# TSOC_GROVEY_I2CHUB.net
KiCad netlist of a schematic drawn in EAGLE
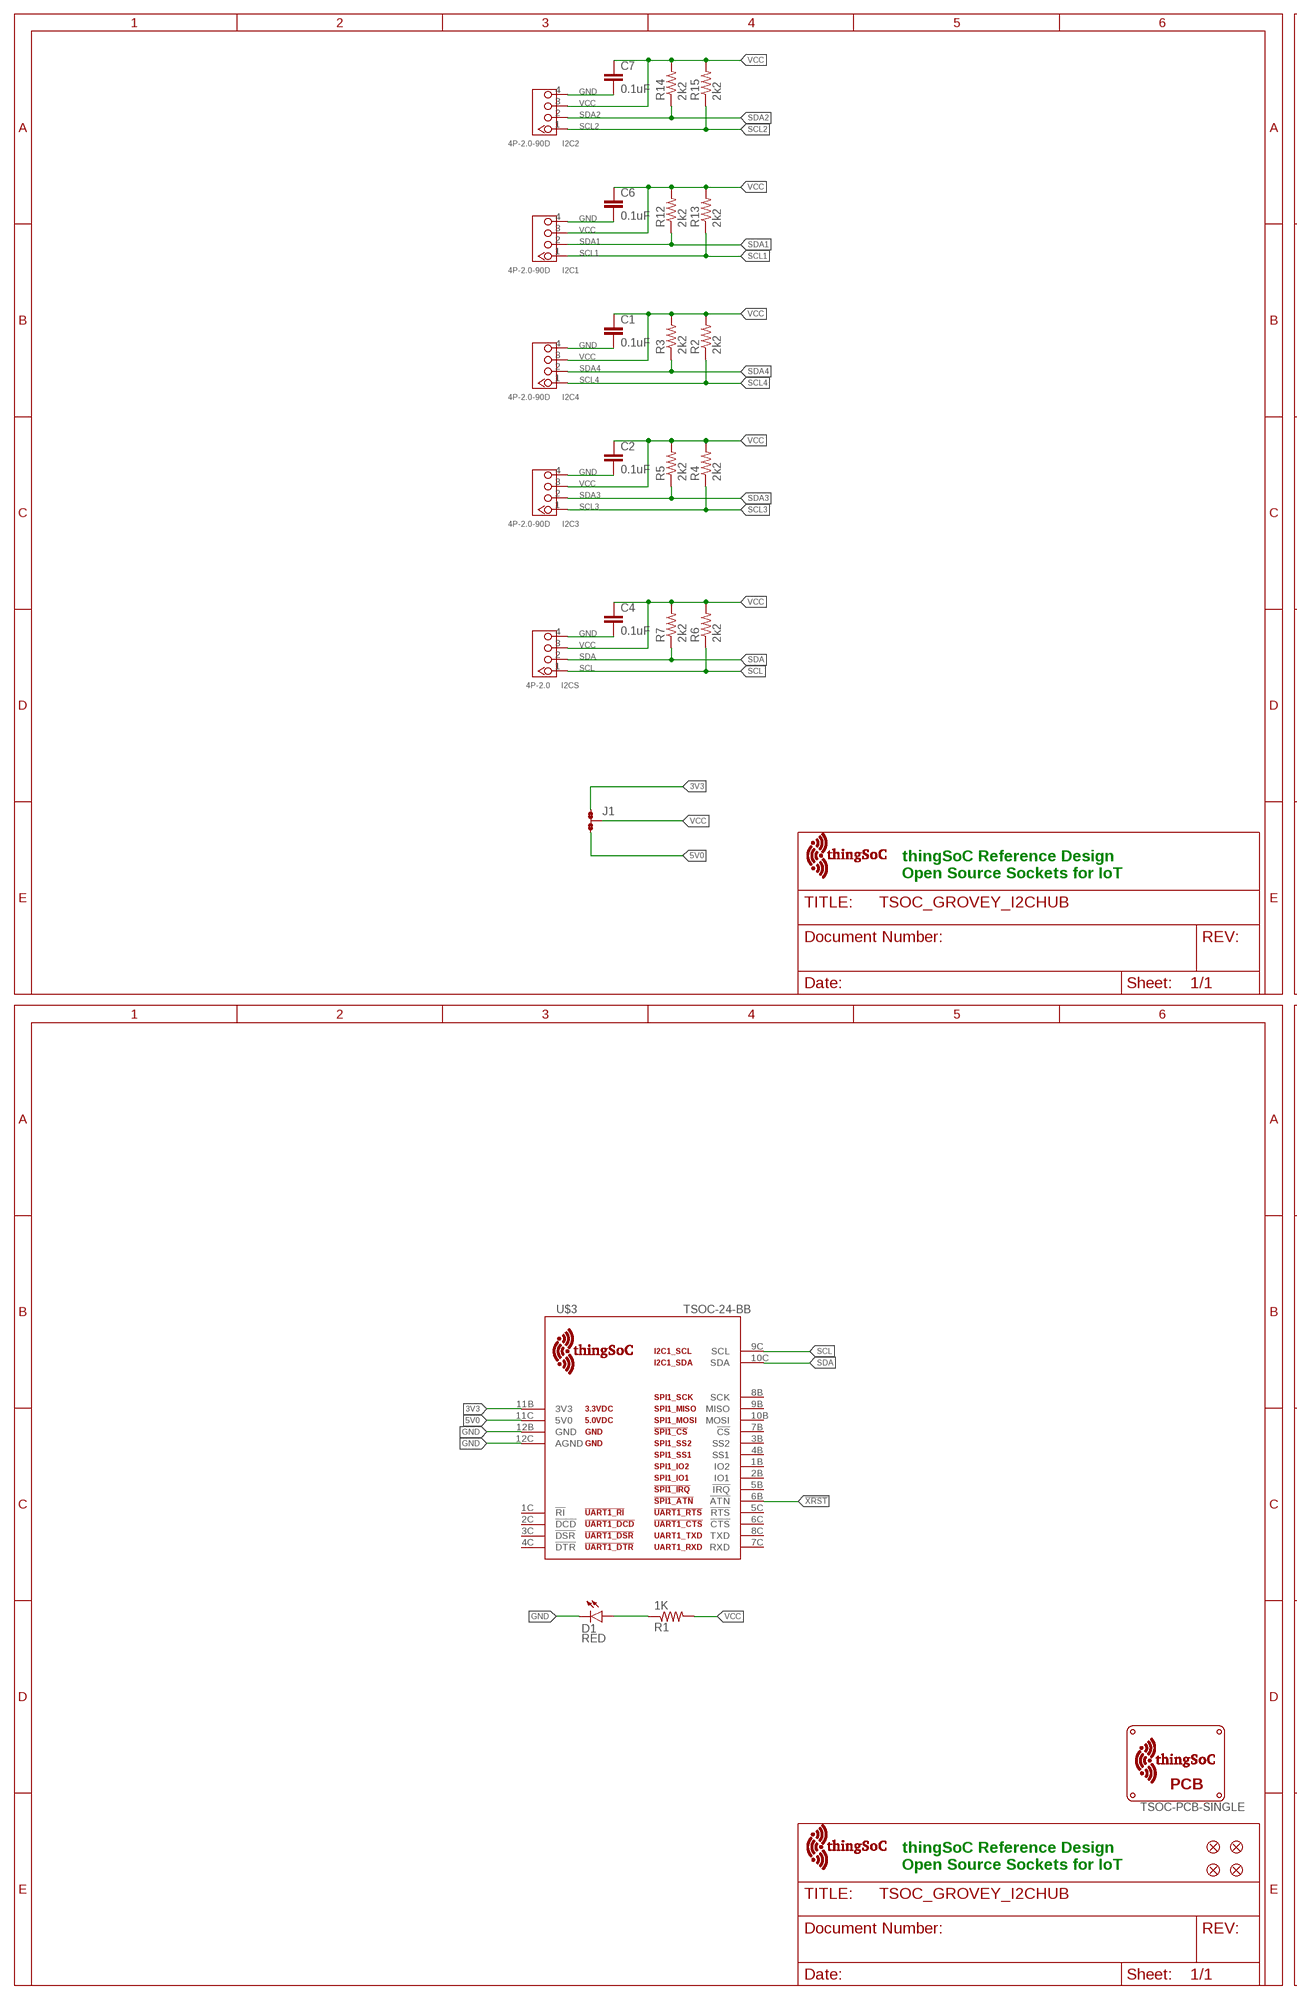
[diagram p0: schematic, sheet 1, part 1 of 2]
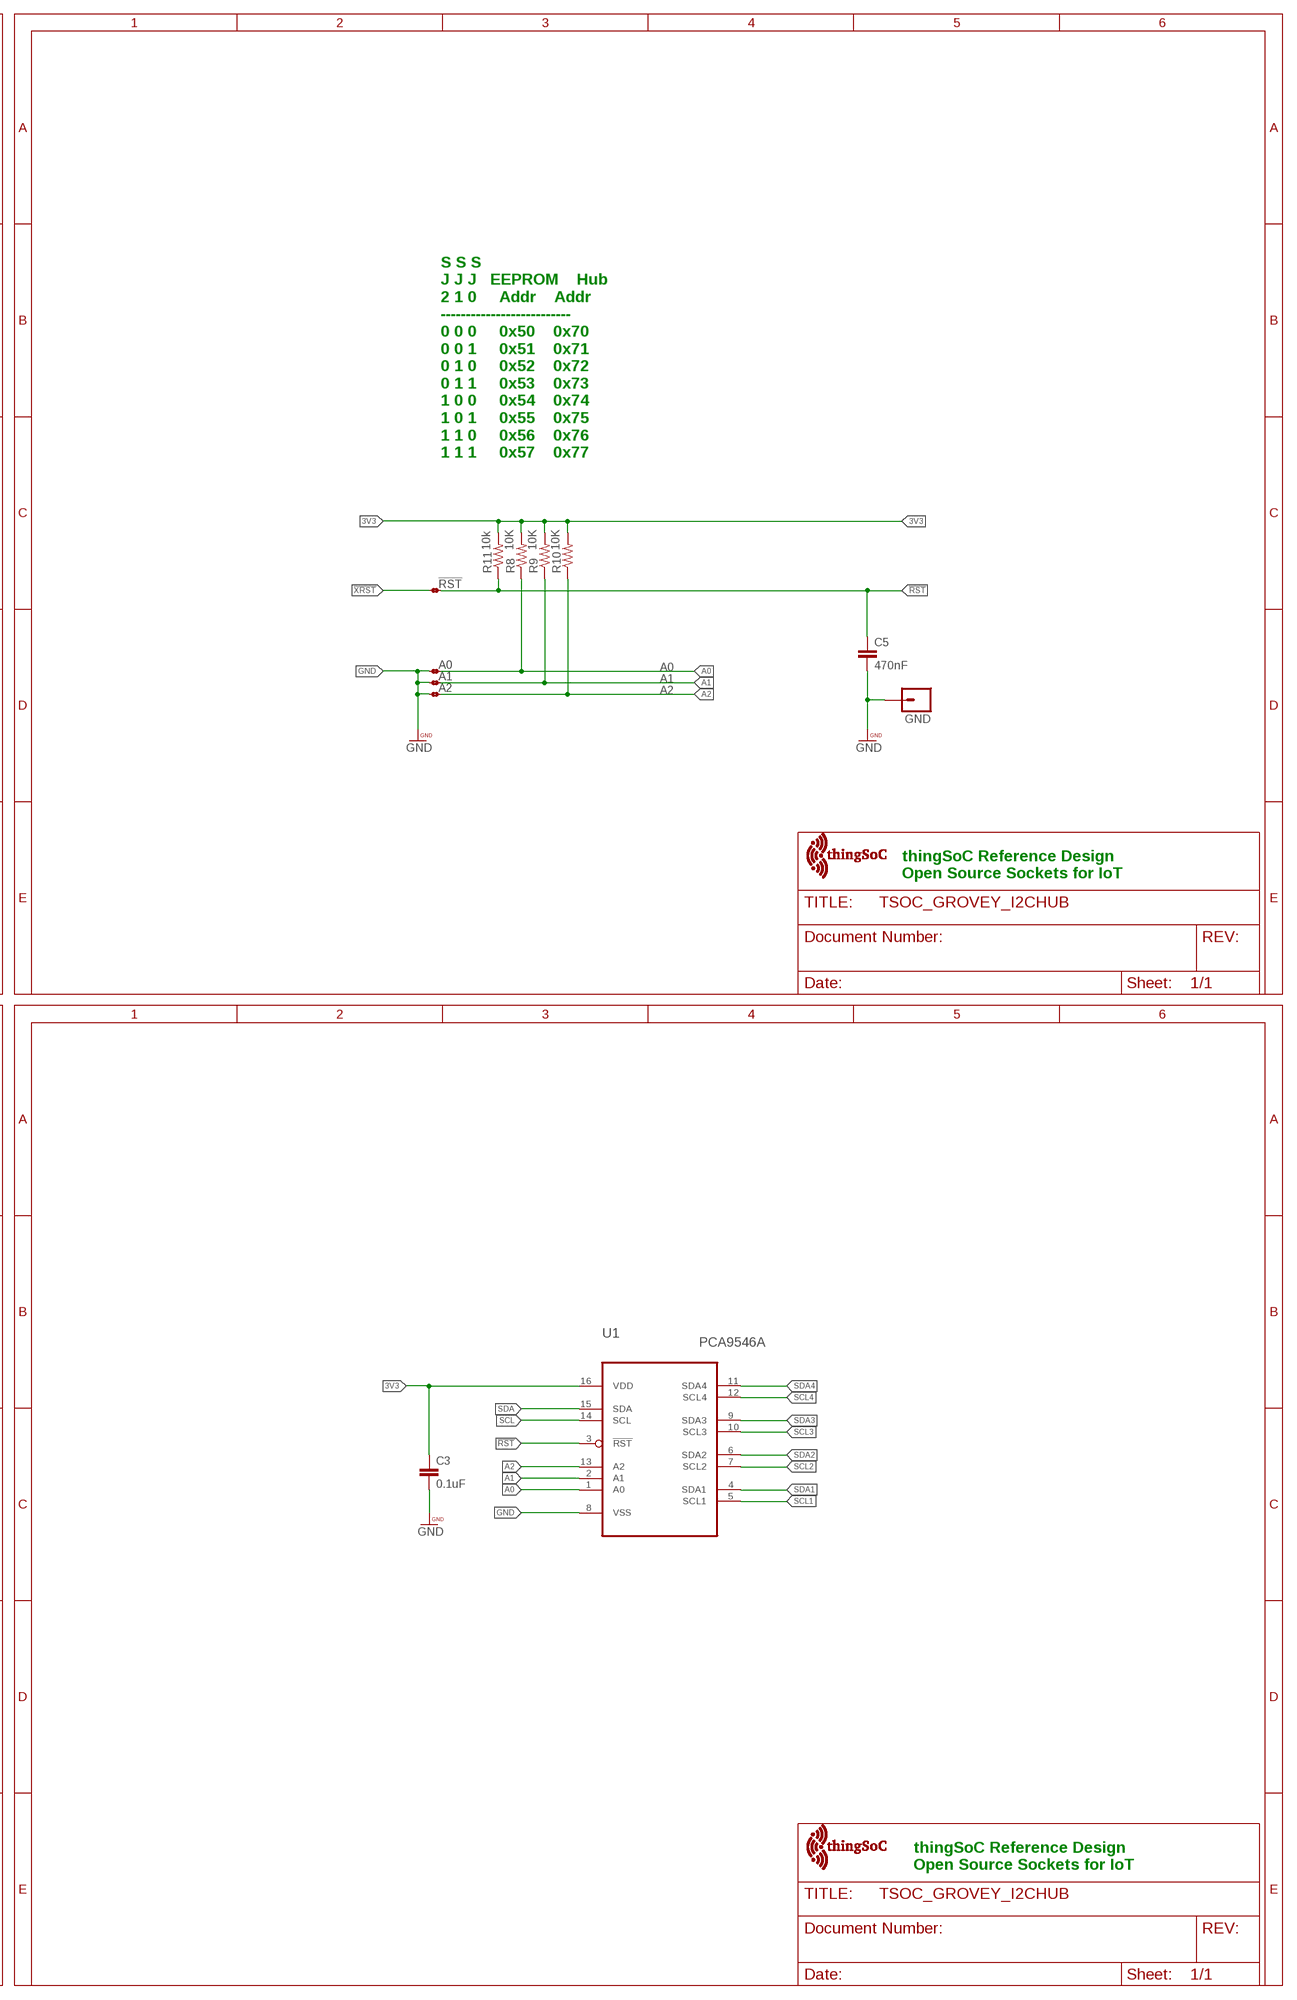
[diagram p1: schematic, sheet 1, part 2 of 2]

(export (version "E")
  (design (tool "Eeschema 10.0.6"))
  (components
    (comp (ref "!RST")
      (value "NO")
      (footprint "eagle-import:JMP-2-NO")
      (libsource (lib "eagle-import") (part "JMP-2-NO"))
    )
    (comp (ref "A0")
      (value "NO")
      (footprint "eagle-import:JMP-2-NO")
      (libsource (lib "eagle-import") (part "JMP-2-NO"))
    )
    (comp (ref "A1")
      (value "NO")
      (footprint "eagle-import:JMP-2-NO")
      (libsource (lib "eagle-import") (part "JMP-2-NO"))
    )
    (comp (ref "A2")
      (value "NO")
      (footprint "eagle-import:JMP-2-NO")
      (libsource (lib "eagle-import") (part "JMP-2-NO"))
    )
    (comp (ref "C1")
      (value "0.1uF")
      (footprint "eagle-import:0603-CAP")
      (libsource (lib "eagle-import") (part "CAP0603-CAP"))
    )
    (comp (ref "C2")
      (value "0.1uF")
      (footprint "eagle-import:0603-CAP")
      (libsource (lib "eagle-import") (part "CAP0603-CAP"))
    )
    (comp (ref "C3")
      (value "0.1uF")
      (footprint "eagle-import:0603-CAP")
      (libsource (lib "eagle-import") (part "CAP0603-CAP"))
    )
    (comp (ref "C4")
      (value "0.1uF")
      (footprint "eagle-import:0603-CAP")
      (libsource (lib "eagle-import") (part "CAP0603-CAP"))
    )
    (comp (ref "C5")
      (value "470nF")
      (footprint "eagle-import:0603-CAP")
      (libsource (lib "eagle-import") (part "CAP0603-CAP"))
    )
    (comp (ref "C6")
      (value "0.1uF")
      (footprint "eagle-import:0603-CAP")
      (libsource (lib "eagle-import") (part "CAP0603-CAP"))
    )
    (comp (ref "C7")
      (value "0.1uF")
      (footprint "eagle-import:0603-CAP")
      (libsource (lib "eagle-import") (part "CAP0603-CAP"))
    )
    (comp (ref "D1")
      (value "RED")
      (footprint "eagle-import:LED-0603")
      (libsource (lib "eagle-import") (part "LED0603"))
    )
    (comp (ref "FID1")
      (value "FIDUCIALUFIDUCIAL")
      (footprint "eagle-import:MICRO-FIDUCIAL")
      (libsource (lib "eagle-import") (part "FIDUCIALUFIDUCIAL"))
    )
    (comp (ref "FID2")
      (value "FIDUCIALUFIDUCIAL")
      (footprint "eagle-import:MICRO-FIDUCIAL")
      (libsource (lib "eagle-import") (part "FIDUCIALUFIDUCIAL"))
    )
    (comp (ref "FID3")
      (value "FIDUCIALUFIDUCIAL")
      (footprint "eagle-import:MICRO-FIDUCIAL")
      (libsource (lib "eagle-import") (part "FIDUCIALUFIDUCIAL"))
    )
    (comp (ref "FID4")
      (value "FIDUCIALUFIDUCIAL")
      (footprint "eagle-import:MICRO-FIDUCIAL")
      (libsource (lib "eagle-import") (part "FIDUCIALUFIDUCIAL"))
    )
    (comp (ref "GND")
      (value "M01PTH")
      (footprint "eagle-import:1X01")
      (libsource (lib "eagle-import") (part "M01PTH"))
    )
    (comp (ref "I2C1")
      (value "4P-2.0-90D")
      (footprint "eagle-import:HW4-2.0-90D")
      (libsource (lib "eagle-import") (part "GROVE-CONNECTOR-DIP-90D(4P-2.0)"))
    )
    (comp (ref "I2C2")
      (value "4P-2.0-90D")
      (footprint "eagle-import:HW4-2.0-90D")
      (libsource (lib "eagle-import") (part "GROVE-CONNECTOR-DIP-90D(4P-2.0)"))
    )
    (comp (ref "I2C3")
      (value "4P-2.0-90D")
      (footprint "eagle-import:HW4-2.0-90D")
      (libsource (lib "eagle-import") (part "GROVE-CONNECTOR-DIP-90D(4P-2.0)"))
    )
    (comp (ref "I2C4")
      (value "4P-2.0-90D")
      (footprint "eagle-import:HW4-2.0-90D")
      (libsource (lib "eagle-import") (part "GROVE-CONNECTOR-DIP-90D(4P-2.0)"))
    )
    (comp (ref "I2CS")
      (value "4P-2.0")
      (footprint "eagle-import:HW4-2.0")
      (libsource (lib "eagle-import") (part "GROVE-CONNECTOR-DIP(4P-2.0)"))
    )
    (comp (ref "J1")
      (value "NO")
      (footprint "eagle-import:JMP-3-NO-PTH-2.54")
      (libsource (lib "eagle-import") (part "JMP-3-NO-PTH"))
    )
    (comp (ref "R1")
      (value "1K")
      (footprint "eagle-import:0603-RES")
      (libsource (lib "eagle-import") (part "RESISTOR_SFE0603-RES"))
    )
    (comp (ref "R2")
      (value "2k2")
      (footprint "eagle-import:0603-RES")
      (libsource (lib "eagle-import") (part "RESISTOR0603-RES"))
    )
    (comp (ref "R3")
      (value "2k2")
      (footprint "eagle-import:0603-RES")
      (libsource (lib "eagle-import") (part "RESISTOR0603-RES"))
    )
    (comp (ref "R4")
      (value "2k2")
      (footprint "eagle-import:0603-RES")
      (libsource (lib "eagle-import") (part "RESISTOR0603-RES"))
    )
    (comp (ref "R5")
      (value "2k2")
      (footprint "eagle-import:0603-RES")
      (libsource (lib "eagle-import") (part "RESISTOR0603-RES"))
    )
    (comp (ref "R6")
      (value "2k2")
      (footprint "eagle-import:0603-RES")
      (libsource (lib "eagle-import") (part "RESISTOR0603-RES"))
    )
    (comp (ref "R7")
      (value "2k2")
      (footprint "eagle-import:0603-RES")
      (libsource (lib "eagle-import") (part "RESISTOR0603-RES"))
    )
    (comp (ref "R8")
      (value "10K")
      (footprint "eagle-import:0603-RES")
      (libsource (lib "eagle-import") (part "RESISTOR0603-RES"))
    )
    (comp (ref "R9")
      (value "10K")
      (footprint "eagle-import:0603-RES")
      (libsource (lib "eagle-import") (part "RESISTOR0603-RES"))
    )
    (comp (ref "R10")
      (value "10K")
      (footprint "eagle-import:0603-RES")
      (libsource (lib "eagle-import") (part "RESISTOR0603-RES"))
    )
    (comp (ref "R11")
      (value "10k")
      (footprint "eagle-import:0603-RES")
      (libsource (lib "eagle-import") (part "RESISTOR0603-RES"))
    )
    (comp (ref "R12")
      (value "2k2")
      (footprint "eagle-import:0603-RES")
      (libsource (lib "eagle-import") (part "RESISTOR0603-RES"))
    )
    (comp (ref "R13")
      (value "2k2")
      (footprint "eagle-import:0603-RES")
      (libsource (lib "eagle-import") (part "RESISTOR0603-RES"))
    )
    (comp (ref "R14")
      (value "2k2")
      (footprint "eagle-import:0603-RES")
      (libsource (lib "eagle-import") (part "RESISTOR0603-RES"))
    )
    (comp (ref "R15")
      (value "2k2")
      (footprint "eagle-import:0603-RES")
      (libsource (lib "eagle-import") (part "RESISTOR0603-RES"))
    )
    (comp (ref "U$1")
      (value "TSOC-LOGO-SMALL")
      (footprint "eagle-import:TSOC-LOGO-SML")
      (libsource (lib "eagle-import") (part "TSOC-LOGO-SMALL"))
    )
    (comp (ref "U$2")
      (value "TSOC-PCB-SINGLE")
      (footprint "eagle-import:TSOC-BB-BRD-DIM")
      (libsource (lib "eagle-import") (part "TSOC-PCB-SINGLE"))
    )
    (comp (ref "U$3")
      (value "TSOC-24-BB")
      (footprint "eagle-import:TSOC-BB-S24")
      (libsource (lib "eagle-import") (part "TSOC-24-BB"))
    )
    (comp (ref "U$101")
      (value "TSOC-LOGO-LRG")
      (footprint "eagle-import:TSOC-LOGO-LRG")
      (libsource (lib "eagle-import") (part "TSOC-LOGO-LRG"))
    )
    (comp (ref "U$102")
      (value "TSOC-LOGO-SMALL")
      (footprint "eagle-import:TSOC-LOGO-SML")
      (libsource (lib "eagle-import") (part "TSOC-LOGO-SMALL"))
    )
    (comp (ref "U$103")
      (value "TSOC-LOGO-SMALL")
      (footprint "eagle-import:TSOC-LOGO-SML")
      (libsource (lib "eagle-import") (part "TSOC-LOGO-SMALL"))
    )
    (comp (ref "U1")
      (value "PCA9546A")
      (footprint "eagle-import:SOP65P640X110-16N")
      (fields (field (name "MPN") "PCA9546APW,112"))
      (libsource (lib "eagle-import") (part "PCA9546A"))
    )
  )
  (nets
    (net (code "1") (name "/~{RST}") (class "Default")
      (node (ref "!RST") (pin "1") (pinfunction "1_1") (pintype "passive"))
      (node (ref "C5") (pin "1") (pinfunction "1_1") (pintype "passive"))
      (node (ref "R11") (pin "1") (pinfunction "1_1") (pintype "passive"))
      (node (ref "U1") (pin "3") (pinfunction "~{RST}_3") (pintype "input"))
    )
    (net (code "2") (name "/~{XRST}") (class "Default")
      (node (ref "!RST") (pin "2") (pinfunction "2_2") (pintype "passive"))
      (node (ref "U$3") (pin "6B") (pinfunction "~{ATN}_6B") (pintype "bidirectional"))
    )
    (net (code "3") (name "3V3") (class "Default")
      (node (ref "C3") (pin "1") (pinfunction "1_1") (pintype "passive"))
      (node (ref "J1") (pin "1") (pinfunction "1_1") (pintype "passive"))
      (node (ref "R10") (pin "2") (pinfunction "2_2") (pintype "passive"))
      (node (ref "R11") (pin "2") (pinfunction "2_2") (pintype "passive"))
      (node (ref "R8") (pin "2") (pinfunction "2_2") (pintype "passive"))
      (node (ref "R9") (pin "2") (pinfunction "2_2") (pintype "passive"))
      (node (ref "U$3") (pin "11B") (pinfunction "3V3_11B") (pintype "bidirectional"))
      (node (ref "U1") (pin "16") (pinfunction "VDD_16") (pintype "power_in"))
    )
    (net (code "4") (name "5V0") (class "Default")
      (node (ref "J1") (pin "3") (pinfunction "3_3") (pintype "passive"))
      (node (ref "U$3") (pin "11C") (pinfunction "5V0_11C") (pintype "bidirectional"))
    )
    (net (code "5") (name "A0") (class "Default")
      (node (ref "A0") (pin "2") (pinfunction "2_2") (pintype "passive"))
      (node (ref "R8") (pin "1") (pinfunction "1_1") (pintype "passive"))
      (node (ref "U1") (pin "1") (pinfunction "A0_1") (pintype "input"))
    )
    (net (code "6") (name "A1") (class "Default")
      (node (ref "A1") (pin "2") (pinfunction "2_2") (pintype "passive"))
      (node (ref "R9") (pin "1") (pinfunction "1_1") (pintype "passive"))
      (node (ref "U1") (pin "2") (pinfunction "A1_2") (pintype "input"))
    )
    (net (code "7") (name "A2") (class "Default")
      (node (ref "A2") (pin "2") (pinfunction "2_2") (pintype "passive"))
      (node (ref "R10") (pin "1") (pinfunction "1_1") (pintype "passive"))
      (node (ref "U1") (pin "13") (pinfunction "A2_13") (pintype "input"))
    )
    (net (code "8") (name "GND") (class "Default")
      (node (ref "A0") (pin "1") (pinfunction "1_1") (pintype "passive"))
      (node (ref "A1") (pin "1") (pinfunction "1_1") (pintype "passive"))
      (node (ref "A2") (pin "1") (pinfunction "1_1") (pintype "passive"))
      (node (ref "C1") (pin "2") (pinfunction "2_2") (pintype "passive"))
      (node (ref "C2") (pin "2") (pinfunction "2_2") (pintype "passive"))
      (node (ref "C3") (pin "2") (pinfunction "2_2") (pintype "passive"))
      (node (ref "C4") (pin "2") (pinfunction "2_2") (pintype "passive"))
      (node (ref "C5") (pin "2") (pinfunction "2_2") (pintype "passive"))
      (node (ref "C6") (pin "2") (pinfunction "2_2") (pintype "passive"))
      (node (ref "C7") (pin "2") (pinfunction "2_2") (pintype "passive"))
      (node (ref "D1") (pin "C") (pinfunction "C_C") (pintype "passive"))
      (node (ref "GND") (pin "1") (pinfunction "1_1") (pintype "passive"))
      (node (ref "I2C1") (pin "4") (pinfunction "4_4") (pintype "bidirectional"))
      (node (ref "I2C2") (pin "4") (pinfunction "4_4") (pintype "bidirectional"))
      (node (ref "I2C3") (pin "4") (pinfunction "4_4") (pintype "bidirectional"))
      (node (ref "I2C4") (pin "4") (pinfunction "4_4") (pintype "bidirectional"))
      (node (ref "I2CS") (pin "4") (pinfunction "4_4") (pintype "bidirectional"))
      (node (ref "U$3") (pin "12B") (pinfunction "GND_12B") (pintype "bidirectional"))
      (node (ref "U$3") (pin "12C") (pinfunction "AGND_12C") (pintype "bidirectional"))
      (node (ref "U1") (pin "8") (pinfunction "VSS_8") (pintype "passive"))
    )
    (net (code "9") (name "Net-(D1-PadA)") (class "Default")
      (node (ref "D1") (pin "A") (pinfunction "A_A") (pintype "passive"))
      (node (ref "R1") (pin "1") (pinfunction "1_1") (pintype "passive"))
    )
    (net (code "10") (name "SCL") (class "Default")
      (node (ref "I2CS") (pin "1") (pinfunction "1_1") (pintype "bidirectional"))
      (node (ref "R6") (pin "1") (pinfunction "1_1") (pintype "passive"))
      (node (ref "U$3") (pin "9C") (pinfunction "SCL_9C") (pintype "bidirectional"))
      (node (ref "U1") (pin "14") (pinfunction "SCL_14") (pintype "bidirectional"))
    )
    (net (code "11") (name "SCL1") (class "Default")
      (node (ref "I2C1") (pin "1") (pinfunction "1_1") (pintype "bidirectional"))
      (node (ref "R13") (pin "1") (pinfunction "1_1") (pintype "passive"))
      (node (ref "U1") (pin "5") (pinfunction "SCL1_5") (pintype "input"))
    )
    (net (code "12") (name "SCL2") (class "Default")
      (node (ref "I2C2") (pin "1") (pinfunction "1_1") (pintype "bidirectional"))
      (node (ref "R15") (pin "1") (pinfunction "1_1") (pintype "passive"))
      (node (ref "U1") (pin "7") (pinfunction "SCL2_7") (pintype "input"))
    )
    (net (code "13") (name "SCL3") (class "Default")
      (node (ref "I2C3") (pin "1") (pinfunction "1_1") (pintype "bidirectional"))
      (node (ref "R4") (pin "1") (pinfunction "1_1") (pintype "passive"))
      (node (ref "U1") (pin "10") (pinfunction "SCL3_10") (pintype "input"))
    )
    (net (code "14") (name "SCL4") (class "Default")
      (node (ref "I2C4") (pin "1") (pinfunction "1_1") (pintype "bidirectional"))
      (node (ref "R2") (pin "1") (pinfunction "1_1") (pintype "passive"))
      (node (ref "U1") (pin "12") (pinfunction "SCL4_12") (pintype "input"))
    )
    (net (code "15") (name "SDA") (class "Default")
      (node (ref "I2CS") (pin "2") (pinfunction "2_2") (pintype "bidirectional"))
      (node (ref "R7") (pin "1") (pinfunction "1_1") (pintype "passive"))
      (node (ref "U$3") (pin "10C") (pinfunction "SDA_10C") (pintype "bidirectional"))
      (node (ref "U1") (pin "15") (pinfunction "SDA_15") (pintype "bidirectional"))
    )
    (net (code "16") (name "SDA1") (class "Default")
      (node (ref "I2C1") (pin "2") (pinfunction "2_2") (pintype "bidirectional"))
      (node (ref "R12") (pin "1") (pinfunction "1_1") (pintype "passive"))
      (node (ref "U1") (pin "4") (pinfunction "SDA1_4") (pintype "input"))
    )
    (net (code "17") (name "SDA2") (class "Default")
      (node (ref "I2C2") (pin "2") (pinfunction "2_2") (pintype "bidirectional"))
      (node (ref "R14") (pin "1") (pinfunction "1_1") (pintype "passive"))
      (node (ref "U1") (pin "6") (pinfunction "SDA2_6") (pintype "input"))
    )
    (net (code "18") (name "SDA3") (class "Default")
      (node (ref "I2C3") (pin "2") (pinfunction "2_2") (pintype "bidirectional"))
      (node (ref "R5") (pin "1") (pinfunction "1_1") (pintype "passive"))
      (node (ref "U1") (pin "9") (pinfunction "SDA3_9") (pintype "input"))
    )
    (net (code "19") (name "SDA4") (class "Default")
      (node (ref "I2C4") (pin "2") (pinfunction "2_2") (pintype "bidirectional"))
      (node (ref "R3") (pin "1") (pinfunction "1_1") (pintype "passive"))
      (node (ref "U1") (pin "11") (pinfunction "SDA4_11") (pintype "input"))
    )
    (net (code "20") (name "VCC") (class "Default")
      (node (ref "C1") (pin "1") (pinfunction "1_1") (pintype "passive"))
      (node (ref "C2") (pin "1") (pinfunction "1_1") (pintype "passive"))
      (node (ref "C4") (pin "1") (pinfunction "1_1") (pintype "passive"))
      (node (ref "C6") (pin "1") (pinfunction "1_1") (pintype "passive"))
      (node (ref "C7") (pin "1") (pinfunction "1_1") (pintype "passive"))
      (node (ref "I2C1") (pin "3") (pinfunction "3_3") (pintype "bidirectional"))
      (node (ref "I2C2") (pin "3") (pinfunction "3_3") (pintype "bidirectional"))
      (node (ref "I2C3") (pin "3") (pinfunction "3_3") (pintype "bidirectional"))
      (node (ref "I2C4") (pin "3") (pinfunction "3_3") (pintype "bidirectional"))
      (node (ref "I2CS") (pin "3") (pinfunction "3_3") (pintype "bidirectional"))
      (node (ref "J1") (pin "2") (pinfunction "2_2") (pintype "passive"))
      (node (ref "R1") (pin "2") (pinfunction "2_2") (pintype "passive"))
      (node (ref "R12") (pin "2") (pinfunction "2_2") (pintype "passive"))
      (node (ref "R13") (pin "2") (pinfunction "2_2") (pintype "passive"))
      (node (ref "R14") (pin "2") (pinfunction "2_2") (pintype "passive"))
      (node (ref "R15") (pin "2") (pinfunction "2_2") (pintype "passive"))
      (node (ref "R2") (pin "2") (pinfunction "2_2") (pintype "passive"))
      (node (ref "R3") (pin "2") (pinfunction "2_2") (pintype "passive"))
      (node (ref "R4") (pin "2") (pinfunction "2_2") (pintype "passive"))
      (node (ref "R5") (pin "2") (pinfunction "2_2") (pintype "passive"))
      (node (ref "R6") (pin "2") (pinfunction "2_2") (pintype "passive"))
      (node (ref "R7") (pin "2") (pinfunction "2_2") (pintype "passive"))
    )
    (net (code "21") (name "unconnected-(U$3-IO1-Pad2B)") (class "Default")
      (node (ref "U$3") (pin "2B") (pinfunction "IO1_2B") (pintype "bidirectional"))
    )
    (net (code "22") (name "unconnected-(U$3-IO2-Pad1B)") (class "Default")
      (node (ref "U$3") (pin "1B") (pinfunction "IO2_1B") (pintype "bidirectional"))
    )
    (net (code "23") (name "unconnected-(U$3-MISO-Pad9B)") (class "Default")
      (node (ref "U$3") (pin "9B") (pinfunction "MISO_9B") (pintype "bidirectional"))
    )
    (net (code "24") (name "unconnected-(U$3-MOSI-Pad10B)") (class "Default")
      (node (ref "U$3") (pin "10B") (pinfunction "MOSI_10B") (pintype "bidirectional"))
    )
    (net (code "25") (name "unconnected-(U$3-RXD-Pad7C)") (class "Default")
      (node (ref "U$3") (pin "7C") (pinfunction "RXD_7C") (pintype "bidirectional"))
    )
    (net (code "26") (name "unconnected-(U$3-SCK-Pad8B)") (class "Default")
      (node (ref "U$3") (pin "8B") (pinfunction "SCK_8B") (pintype "bidirectional"))
    )
    (net (code "27") (name "unconnected-(U$3-SS1-Pad4B)") (class "Default")
      (node (ref "U$3") (pin "4B") (pinfunction "SS1_4B") (pintype "bidirectional"))
    )
    (net (code "28") (name "unconnected-(U$3-SS2-Pad3B)") (class "Default")
      (node (ref "U$3") (pin "3B") (pinfunction "SS2_3B") (pintype "bidirectional"))
    )
    (net (code "29") (name "unconnected-(U$3-TXD-Pad8C)") (class "Default")
      (node (ref "U$3") (pin "8C") (pinfunction "TXD_8C") (pintype "bidirectional"))
    )
    (net (code "30") (name "unconnected-(U$3-~{CS}-Pad7B)") (class "Default")
      (node (ref "U$3") (pin "7B") (pinfunction "~{CS}_7B") (pintype "bidirectional"))
    )
    (net (code "31") (name "unconnected-(U$3-~{CTS}-Pad6C)") (class "Default")
      (node (ref "U$3") (pin "6C") (pinfunction "~{CTS}_6C") (pintype "bidirectional"))
    )
    (net (code "32") (name "unconnected-(U$3-~{DCD}-Pad2C)") (class "Default")
      (node (ref "U$3") (pin "2C") (pinfunction "~{DCD}_2C") (pintype "bidirectional"))
    )
    (net (code "33") (name "unconnected-(U$3-~{DSR}-Pad3C)") (class "Default")
      (node (ref "U$3") (pin "3C") (pinfunction "~{DSR}_3C") (pintype "bidirectional"))
    )
    (net (code "34") (name "unconnected-(U$3-~{DTR}-Pad4C)") (class "Default")
      (node (ref "U$3") (pin "4C") (pinfunction "~{DTR}_4C") (pintype "bidirectional"))
    )
    (net (code "35") (name "unconnected-(U$3-~{IRQ}-Pad5B)") (class "Default")
      (node (ref "U$3") (pin "5B") (pinfunction "~{IRQ}_5B") (pintype "bidirectional"))
    )
    (net (code "36") (name "unconnected-(U$3-~{RI}-Pad1C)") (class "Default")
      (node (ref "U$3") (pin "1C") (pinfunction "~{RI}_1C") (pintype "bidirectional"))
    )
    (net (code "37") (name "unconnected-(U$3-~{RTS}-Pad5C)") (class "Default")
      (node (ref "U$3") (pin "5C") (pinfunction "~{RTS}_5C") (pintype "bidirectional"))
    )
  )
)
